# st-link-v2.net
KiCad netlist of a schematic drawn in Altium Designer
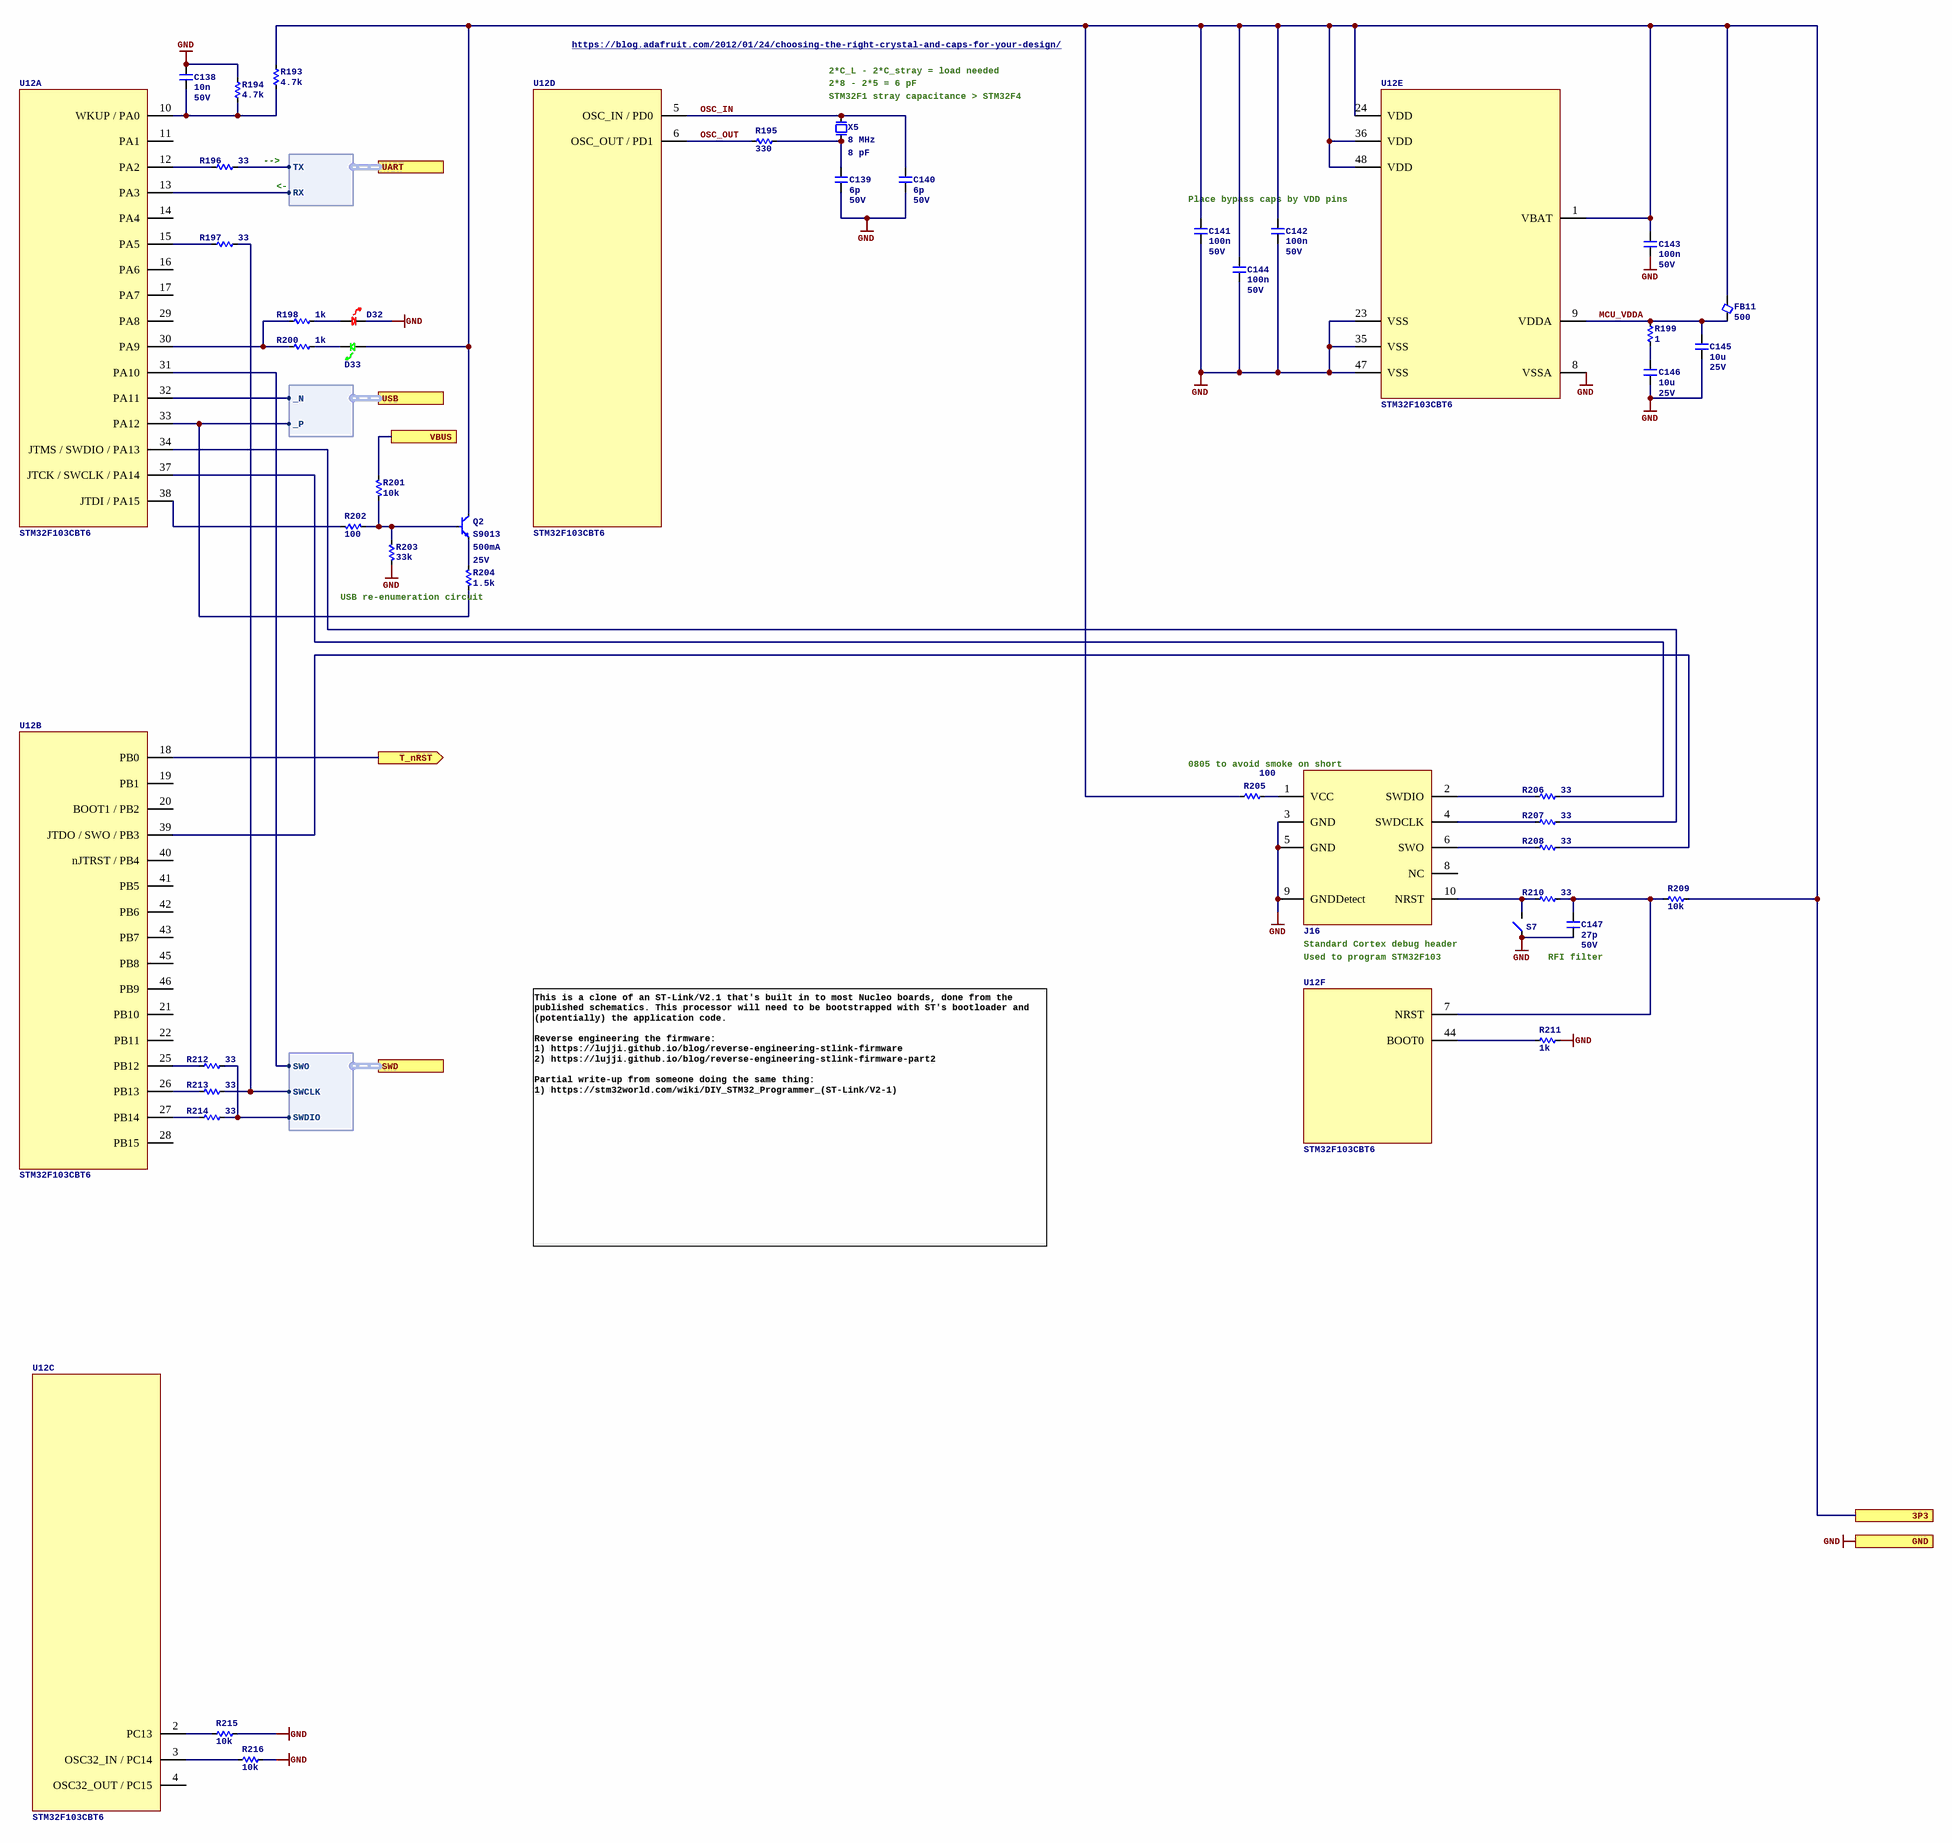
[diagram p0: st-link-v2.SchDoc]

(export (version "E")
  (design (tool "Eeschema 10.0.6"))
  (components
    (comp (ref "C138")
      (value "CL05B103KB5NNNC")
      (footprint "C0402")
      (fields
        (field (name "CAPACITANCE") "10n")
        (field (name "MANUFACTURER") "Samsung Electro-Mechanics")
        (field (name "VOLTAGE RATING") "50V")
      )
      (libsource (lib "database") (part "__template_cap"))
    )
    (comp (ref "C139")
      (value "0402CG6R0C500NT")
      (footprint "C0402")
      (fields
        (field (name "CAPACITANCE") "6p")
        (field (name "MANUFACTURER") "FH(Guangdong Fenghua Advanced Tech)")
        (field (name "VOLTAGE RATING") "50V")
      )
      (libsource (lib "database") (part "__template_cap"))
    )
    (comp (ref "C140")
      (value "0402CG6R0C500NT")
      (footprint "C0402")
      (fields
        (field (name "CAPACITANCE") "6p")
        (field (name "MANUFACTURER") "FH(Guangdong Fenghua Advanced Tech)")
        (field (name "VOLTAGE RATING") "50V")
      )
      (libsource (lib "database") (part "__template_cap"))
    )
    (comp (ref "C141")
      (value "CL05B104KB54PNC")
      (footprint "C0402")
      (fields
        (field (name "CAPACITANCE") "100n")
        (field (name "MANUFACTURER") "Samsung Electro-Mechanics")
        (field (name "VOLTAGE RATING") "50V")
      )
      (libsource (lib "database") (part "__template_cap"))
    )
    (comp (ref "C142")
      (value "CL05B104KB54PNC")
      (footprint "C0402")
      (fields
        (field (name "CAPACITANCE") "100n")
        (field (name "MANUFACTURER") "Samsung Electro-Mechanics")
        (field (name "VOLTAGE RATING") "50V")
      )
      (libsource (lib "database") (part "__template_cap"))
    )
    (comp (ref "C143")
      (value "CL05B104KB54PNC")
      (footprint "C0402")
      (fields
        (field (name "CAPACITANCE") "100n")
        (field (name "MANUFACTURER") "Samsung Electro-Mechanics")
        (field (name "VOLTAGE RATING") "50V")
      )
      (libsource (lib "database") (part "__template_cap"))
    )
    (comp (ref "C144")
      (value "CL05B104KB54PNC")
      (footprint "C0402")
      (fields
        (field (name "CAPACITANCE") "100n")
        (field (name "MANUFACTURER") "Samsung Electro-Mechanics")
        (field (name "VOLTAGE RATING") "50V")
      )
      (libsource (lib "database") (part "__template_cap"))
    )
    (comp (ref "C145")
      (value "CL10A106MA8NRNC")
      (footprint "C0603")
      (fields
        (field (name "CAPACITANCE") "10u")
        (field (name "MANUFACTURER") "Samsung Electro-Mechanics")
        (field (name "VOLTAGE RATING") "25V")
      )
      (libsource (lib "database") (part "__template_cap"))
    )
    (comp (ref "C146")
      (value "CL21B106KAYQNNE")
      (footprint "C0805")
      (fields
        (field (name "CAPACITANCE") "10u")
        (field (name "MANUFACTURER") "Samsung Electro-Mechanics")
        (field (name "VOLTAGE RATING") "25V")
      )
      (libsource (lib "database") (part "__template_cap"))
    )
    (comp (ref "C147")
      (value "0402CG270J500NT")
      (footprint "C0402")
      (fields
        (field (name "CAPACITANCE") "27p")
        (field (name "MANUFACTURER") "FH(Guangdong Fenghua Advanced Tech)")
        (field (name "VOLTAGE RATING") "50V")
      )
      (libsource (lib "database") (part "__template_cap"))
    )
    (comp (ref "D32")
      (value "LTST-C190KRKT")
      (footprint "LED_0603P_RED")
      (description "LED SUPER RED CLEAR 0603 SMD")
      (fields (field (name "MANUFACTURER") "Lite-On Inc"))
      (libsource (lib "SSCP") (part "LED_0603_RED_LTST-C190KRKT"))
    )
    (comp (ref "D33")
      (value "LTST-C190GKT")
      (footprint "LED_0603P_GREEN")
      (description "LED GREEN CLEAR 0603 SMD")
      (fields (field (name "MANUFACTURER") "Lite-On Inc"))
      (libsource (lib "SSCP") (part "LED_0603_GREEN_LTST-C190GKT"))
    )
    (comp (ref "FB11")
      (value "BLM15AX601SN1D")
      (footprint "FB0402")
      (fields (field (name "MANUFACTURER") "Murata Electronics") (field (name "CURRENT RATING (MA)") "500"))
      (libsource (lib "database") (part "__template_fb"))
    )
    (comp (ref "J16")
      (value "FTSH-105-01-L-DV-K")
      (footprint "FTSH-105-01-L-DV-K_KEYED")
      (description "CONN HEADER 10 POS DUAL .05\" SMD")
      (fields (field (name "MANUFACTURER") "Samtec Inc"))
      (libsource (lib "SSCP") (part "CONN_SWD_CORTEX_DEBUG"))
    )
    (comp (ref "Q2")
      (value "S9013")
      (footprint "3SOT23")
      (description "Bipolar (BJT) Transistor NPN 25 V 500 mA 150MHz 300 mW Surface Mount SOT-23")
      (fields
        (field (name "MANUFACTURER") "Shenzhen Slkormicro Semicon Co., Ltd.")
        (field (name "CURRENT") "500mA")
        (field (name "VOLTAGE") "25V")
      )
      (libsource (lib "SSCP") (part "NPN_25V_S9013"))
    )
    (comp (ref "R193")
      (value "4.7k")
      (footprint "R0402")
      (fields
        (field (name "TOLERANCE") "1%")
        (field (name "MANUFACTURER PART NUMBER") "0402WGF4701TCE")
        (field (name "MANUFACTURER") "UNI-ROYAL(Uniroyal Elec)")
      )
      (libsource (lib "database") (part "__template_resistor"))
    )
    (comp (ref "R194")
      (value "4.7k")
      (footprint "R0402")
      (fields
        (field (name "TOLERANCE") "1%")
        (field (name "MANUFACTURER PART NUMBER") "0402WGF4701TCE")
        (field (name "MANUFACTURER") "UNI-ROYAL(Uniroyal Elec)")
      )
      (libsource (lib "database") (part "__template_resistor"))
    )
    (comp (ref "R195")
      (value "330")
      (footprint "R0402")
      (fields
        (field (name "TOLERANCE") "1%")
        (field (name "MANUFACTURER PART NUMBER") "0402WGF3300TCE")
        (field (name "MANUFACTURER") "UNI-ROYAL(Uniroyal Elec)")
      )
      (libsource (lib "database") (part "__template_resistor"))
    )
    (comp (ref "R196")
      (value "33")
      (footprint "R0402")
      (fields
        (field (name "TOLERANCE") "1%")
        (field (name "MANUFACTURER PART NUMBER") "0402WGF330JTCE")
        (field (name "MANUFACTURER") "UNI-ROYAL(Uniroyal Elec)")
      )
      (libsource (lib "database") (part "__template_resistor"))
    )
    (comp (ref "R197")
      (value "33")
      (footprint "R0402")
      (fields
        (field (name "TOLERANCE") "1%")
        (field (name "MANUFACTURER PART NUMBER") "0402WGF330JTCE")
        (field (name "MANUFACTURER") "UNI-ROYAL(Uniroyal Elec)")
      )
      (libsource (lib "database") (part "__template_resistor"))
    )
    (comp (ref "R198")
      (value "1k")
      (footprint "R0402")
      (fields
        (field (name "TOLERANCE") "1%")
        (field (name "MANUFACTURER PART NUMBER") "0402WGF1001TCE")
        (field (name "MANUFACTURER") "UNI-ROYAL(Uniroyal Elec)")
      )
      (libsource (lib "database") (part "__template_resistor"))
    )
    (comp (ref "R199")
      (value "1")
      (footprint "R0402")
      (fields
        (field (name "TOLERANCE") "1%")
        (field (name "MANUFACTURER PART NUMBER") "CRCW04021R00FKED")
        (field (name "MANUFACTURER") "Vishay Intertech")
      )
      (libsource (lib "database") (part "__template_resistor"))
    )
    (comp (ref "R200")
      (value "1k")
      (footprint "R0402")
      (fields
        (field (name "TOLERANCE") "1%")
        (field (name "MANUFACTURER PART NUMBER") "0402WGF1001TCE")
        (field (name "MANUFACTURER") "UNI-ROYAL(Uniroyal Elec)")
      )
      (libsource (lib "database") (part "__template_resistor"))
    )
    (comp (ref "R201")
      (value "10k")
      (footprint "R0402")
      (fields
        (field (name "TOLERANCE") "1%")
        (field (name "MANUFACTURER PART NUMBER") "0402WGF1002TCE")
        (field (name "MANUFACTURER") "UNI-ROYAL(Uniroyal Elec)")
      )
      (libsource (lib "database") (part "__template_resistor"))
    )
    (comp (ref "R202")
      (value "100")
      (footprint "R0402")
      (fields
        (field (name "TOLERANCE") "1%")
        (field (name "MANUFACTURER PART NUMBER") "RC0402FR-07100RL")
        (field (name "MANUFACTURER") "YAGEO")
      )
      (libsource (lib "database") (part "__template_resistor"))
    )
    (comp (ref "R203")
      (value "33k")
      (footprint "R0402")
      (fields
        (field (name "TOLERANCE") "1%")
        (field (name "MANUFACTURER PART NUMBER") "0402WGF3302TCE")
        (field (name "MANUFACTURER") "UNI-ROYAL(Uniroyal Elec)")
      )
      (libsource (lib "database") (part "__template_resistor"))
    )
    (comp (ref "R204")
      (value "1.5k")
      (footprint "R0402")
      (fields
        (field (name "TOLERANCE") "1%")
        (field (name "MANUFACTURER PART NUMBER") "0402WGF1501TCE")
        (field (name "MANUFACTURER") "UNI-ROYAL(Uniroyal Elec)")
      )
      (libsource (lib "database") (part "__template_resistor"))
    )
    (comp (ref "R205")
      (value "100")
      (footprint "R0805")
      (fields
        (field (name "TOLERANCE") "1%")
        (field (name "MANUFACTURER PART NUMBER") "ERJP06F1000V")
        (field (name "MANUFACTURER") "PANASONIC")
      )
      (libsource (lib "database") (part "__template_resistor"))
    )
    (comp (ref "R206")
      (value "33")
      (footprint "R0402")
      (fields
        (field (name "TOLERANCE") "1%")
        (field (name "MANUFACTURER PART NUMBER") "0402WGF330JTCE")
        (field (name "MANUFACTURER") "UNI-ROYAL(Uniroyal Elec)")
      )
      (libsource (lib "database") (part "__template_resistor"))
    )
    (comp (ref "R207")
      (value "33")
      (footprint "R0402")
      (fields
        (field (name "TOLERANCE") "1%")
        (field (name "MANUFACTURER PART NUMBER") "0402WGF330JTCE")
        (field (name "MANUFACTURER") "UNI-ROYAL(Uniroyal Elec)")
      )
      (libsource (lib "database") (part "__template_resistor"))
    )
    (comp (ref "R208")
      (value "33")
      (footprint "R0402")
      (fields
        (field (name "TOLERANCE") "1%")
        (field (name "MANUFACTURER PART NUMBER") "0402WGF330JTCE")
        (field (name "MANUFACTURER") "UNI-ROYAL(Uniroyal Elec)")
      )
      (libsource (lib "database") (part "__template_resistor"))
    )
    (comp (ref "R209")
      (value "10k")
      (footprint "R0402")
      (fields
        (field (name "TOLERANCE") "1%")
        (field (name "MANUFACTURER PART NUMBER") "0402WGF1002TCE")
        (field (name "MANUFACTURER") "UNI-ROYAL(Uniroyal Elec)")
      )
      (libsource (lib "database") (part "__template_resistor"))
    )
    (comp (ref "R210")
      (value "33")
      (footprint "R0402")
      (fields
        (field (name "TOLERANCE") "1%")
        (field (name "MANUFACTURER PART NUMBER") "0402WGF330JTCE")
        (field (name "MANUFACTURER") "UNI-ROYAL(Uniroyal Elec)")
      )
      (libsource (lib "database") (part "__template_resistor"))
    )
    (comp (ref "R211")
      (value "1k")
      (footprint "R0402")
      (fields
        (field (name "TOLERANCE") "1%")
        (field (name "MANUFACTURER PART NUMBER") "0402WGF1001TCE")
        (field (name "MANUFACTURER") "UNI-ROYAL(Uniroyal Elec)")
      )
      (libsource (lib "database") (part "__template_resistor"))
    )
    (comp (ref "R212")
      (value "33")
      (footprint "R0402")
      (fields
        (field (name "TOLERANCE") "1%")
        (field (name "MANUFACTURER PART NUMBER") "0402WGF330JTCE")
        (field (name "MANUFACTURER") "UNI-ROYAL(Uniroyal Elec)")
      )
      (libsource (lib "database") (part "__template_resistor"))
    )
    (comp (ref "R213")
      (value "33")
      (footprint "R0402")
      (fields
        (field (name "TOLERANCE") "1%")
        (field (name "MANUFACTURER PART NUMBER") "0402WGF330JTCE")
        (field (name "MANUFACTURER") "UNI-ROYAL(Uniroyal Elec)")
      )
      (libsource (lib "database") (part "__template_resistor"))
    )
    (comp (ref "R214")
      (value "33")
      (footprint "R0402")
      (fields
        (field (name "TOLERANCE") "1%")
        (field (name "MANUFACTURER PART NUMBER") "0402WGF330JTCE")
        (field (name "MANUFACTURER") "UNI-ROYAL(Uniroyal Elec)")
      )
      (libsource (lib "database") (part "__template_resistor"))
    )
    (comp (ref "R215")
      (value "10k")
      (footprint "R0402")
      (fields
        (field (name "TOLERANCE") "1%")
        (field (name "MANUFACTURER PART NUMBER") "0402WGF1002TCE")
        (field (name "MANUFACTURER") "UNI-ROYAL(Uniroyal Elec)")
      )
      (libsource (lib "database") (part "__template_resistor"))
    )
    (comp (ref "R216")
      (value "10k")
      (footprint "R0402")
      (fields
        (field (name "TOLERANCE") "1%")
        (field (name "MANUFACTURER PART NUMBER") "0402WGF1002TCE")
        (field (name "MANUFACTURER") "UNI-ROYAL(Uniroyal Elec)")
      )
      (libsource (lib "database") (part "__template_resistor"))
    )
    (comp (ref "S7")
      (value "TS-1092S-B3D2-G")
      (footprint "SWITCH_TS-1092S-B3D2-G")
      (description "SWITCH TACTILE SPST-NO")
      (fields (field (name "MANUFACTURER") "Yuandi"))
      (libsource (lib "SSCP") (part "SWITCH_TS-1092S-B3D2-G"))
    )
    (comp (ref "U12")
      (value "STM32F103CBT6")
      (footprint "48TQFP7")
      (description "ARM Cortex-M3 STM32 F1 Microcontroller 32-Bit 72MHz 128kB FLASH LQFP48 STM32F103CBT6")
      (fields (field (name "MANUFACTURER") "STMicroelectronics"))
      (libsource (lib "SSCP") (part "MCU_STM32F103CBT6"))
    )
    (comp (ref "X5")
      (value "ECS-80-8-33Q-JES-TR")
      (footprint "4_SMD_3.2X2.5MM")
      (description "8 MHz ±20ppm Crystal 8pF 500 Ohms 4-SMD, No Lead")
      (fields
        (field (name "MANUFACTURER") "ECS Inc.")
        (field (name "FREQUENCY") "8 MHz")
        (field (name "CAPACITANCE") "8 pF")
      )
      (libsource (lib "SSCP") (part "XTAL_8MHZ_ECS-80-8-33Q-JES-TR"))
    )
  )
  (nets
    (net (code "4") (name "/3P3") (class "Default")
      (node (ref "C141") (pin "1") (pintype "passive"))
      (node (ref "C142") (pin "1") (pintype "passive"))
      (node (ref "C143") (pin "1") (pintype "passive"))
      (node (ref "C144") (pin "1") (pintype "passive"))
      (node (ref "D33") (pin "2") (pintype "passive"))
      (node (ref "FB11") (pin "2") (pintype "passive"))
      (node (ref "Q2") (pin "3") (pinfunction "C_3") (pintype "passive"))
      (node (ref "R193") (pin "2") (pintype "passive"))
      (node (ref "R205") (pin "2") (pintype "passive"))
      (node (ref "R209") (pin "1") (pintype "passive"))
      (node (ref "U12") (pin "1") (pinfunction "VBAT_1") (pintype "passive"))
      (node (ref "U12") (pin "24") (pinfunction "VDD_24") (pintype "passive"))
      (node (ref "U12") (pin "36") (pinfunction "VDD_36") (pintype "passive"))
      (node (ref "U12") (pin "48") (pinfunction "VDD_48") (pintype "passive"))
    )
    (net (code "5") (name "/MCU_VDDA") (class "Default")
      (node (ref "C145") (pin "1") (pintype "passive"))
      (node (ref "FB11") (pin "1") (pintype "passive"))
      (node (ref "R199") (pin "2") (pintype "passive"))
      (node (ref "U12") (pin "9") (pinfunction "VDDA_9") (pintype "passive"))
    )
    (net (code "6") (name "/OSC_IN") (class "Default")
      (node (ref "C140") (pin "1") (pintype "passive"))
      (node (ref "U12") (pin "5") (pinfunction "OSC_IN_/_PD0_5") (pintype "passive"))
      (node (ref "X5") (pin "3") (pinfunction "3_3") (pintype "passive"))
    )
    (net (code "7") (name "/OSC_OUT") (class "Default")
      (node (ref "R195") (pin "1") (pintype "passive"))
      (node (ref "U12") (pin "6") (pinfunction "OSC_OUT_/_PD1_6") (pintype "passive"))
    )
    (net (code "8") (name "/RX") (class "Default")
      (node (ref "U12") (pin "13") (pinfunction "PA3_13") (pintype "passive"))
    )
    (net (code "9") (name "/SWCLK") (class "Default")
      (node (ref "R197") (pin "1") (pintype "passive"))
      (node (ref "R213") (pin "1") (pintype "passive"))
    )
    (net (code "10") (name "/SWDIO") (class "Default")
      (node (ref "R212") (pin "1") (pintype "passive"))
      (node (ref "R214") (pin "1") (pintype "passive"))
    )
    (net (code "11") (name "/SWO") (class "Default")
      (node (ref "U12") (pin "31") (pinfunction "PA10_31") (pintype "passive"))
    )
    (net (code "12") (name "/TX") (class "Default") (node (ref "R196") (pin "1") (pintype "passive")))
    (net (code "13") (name "/T_nRST") (class "Default")
      (node (ref "U12") (pin "18") (pinfunction "PB0_18") (pintype "passive"))
    )
    (net (code "14") (name "/VBUS") (class "Default") (node (ref "R201") (pin "1") (pintype "passive")))
    (net (code "15") (name "/_N") (class "Default")
      (node (ref "U12") (pin "32") (pinfunction "PA11_32") (pintype "passive"))
    )
    (net (code "16") (name "/_P") (class "Default")
      (node (ref "R204") (pin "2") (pintype "passive"))
      (node (ref "U12") (pin "33") (pinfunction "PA12_33") (pintype "passive"))
    )
    (net (code "20") (name "GND") (class "Default")
      (node (ref "C138") (pin "1") (pintype "passive"))
      (node (ref "C139") (pin "2") (pintype "passive"))
      (node (ref "C140") (pin "2") (pintype "passive"))
      (node (ref "C141") (pin "2") (pintype "passive"))
      (node (ref "C142") (pin "2") (pintype "passive"))
      (node (ref "C143") (pin "2") (pintype "passive"))
      (node (ref "C144") (pin "2") (pintype "passive"))
      (node (ref "C145") (pin "2") (pintype "passive"))
      (node (ref "C146") (pin "2") (pintype "passive"))
      (node (ref "C147") (pin "2") (pintype "passive"))
      (node (ref "D32") (pin "1") (pintype "passive"))
      (node (ref "J16") (pin "3") (pinfunction "GND_3") (pintype "passive"))
      (node (ref "J16") (pin "5") (pinfunction "GND_5") (pintype "passive"))
      (node (ref "J16") (pin "9") (pinfunction "GNDDetect_9") (pintype "passive"))
      (node (ref "R194") (pin "2") (pintype "passive"))
      (node (ref "R203") (pin "2") (pintype "passive"))
      (node (ref "R211") (pin "2") (pintype "passive"))
      (node (ref "R215") (pin "2") (pintype "passive"))
      (node (ref "R216") (pin "2") (pintype "passive"))
      (node (ref "S7") (pin "1") (pintype "passive"))
      (node (ref "U12") (pin "23") (pinfunction "VSS_23") (pintype "passive"))
      (node (ref "U12") (pin "35") (pinfunction "VSS_35") (pintype "passive"))
      (node (ref "U12") (pin "47") (pinfunction "VSS_47") (pintype "passive"))
      (node (ref "U12") (pin "8") (pinfunction "VSSA_8") (pintype "passive"))
    )
    (net (code "21") (name "Net-(C139-Pad1)") (class "Default")
      (node (ref "C139") (pin "1") (pintype "passive"))
      (node (ref "R195") (pin "2") (pintype "passive"))
      (node (ref "X5") (pin "1") (pinfunction "1_1") (pintype "passive"))
    )
    (net (code "22") (name "Net-(C146-Pad1)") (class "Default")
      (node (ref "C146") (pin "1") (pintype "passive"))
      (node (ref "R199") (pin "1") (pintype "passive"))
    )
    (net (code "23") (name "Net-(D32-Pad2)") (class "Default")
      (node (ref "D32") (pin "2") (pintype "passive"))
      (node (ref "R198") (pin "1") (pintype "passive"))
    )
    (net (code "24") (name "Net-(D33-Pad1)") (class "Default")
      (node (ref "D33") (pin "1") (pintype "passive"))
      (node (ref "R200") (pin "1") (pintype "passive"))
    )
    (net (code "25") (name "Net-(J16-NRST)") (class "Default")
      (node (ref "J16") (pin "10") (pinfunction "NRST_10") (pintype "passive"))
      (node (ref "R210") (pin "2") (pintype "passive"))
      (node (ref "S7") (pin "2") (pintype "passive"))
    )
    (net (code "26") (name "Net-(J16-SWDCLK)") (class "Default")
      (node (ref "J16") (pin "4") (pinfunction "SWDCLK_4") (pintype "passive"))
      (node (ref "R207") (pin "2") (pintype "passive"))
    )
    (net (code "27") (name "Net-(J16-SWDIO)") (class "Default")
      (node (ref "J16") (pin "2") (pinfunction "SWDIO_2") (pintype "passive"))
      (node (ref "R206") (pin "2") (pintype "passive"))
    )
    (net (code "28") (name "Net-(J16-SWO)") (class "Default")
      (node (ref "J16") (pin "6") (pinfunction "SWO_6") (pintype "passive"))
      (node (ref "R208") (pin "2") (pintype "passive"))
    )
    (net (code "29") (name "Net-(J16-VCC)") (class "Default")
      (node (ref "J16") (pin "1") (pinfunction "VCC_1") (pintype "passive"))
      (node (ref "R205") (pin "1") (pintype "passive"))
    )
    (net (code "30") (name "Net-(Q2-B)") (class "Default")
      (node (ref "Q2") (pin "1") (pinfunction "B_1") (pintype "passive"))
      (node (ref "R201") (pin "2") (pintype "passive"))
      (node (ref "R202") (pin "1") (pintype "passive"))
      (node (ref "R203") (pin "1") (pintype "passive"))
    )
    (net (code "31") (name "Net-(Q2-E)") (class "Default")
      (node (ref "Q2") (pin "2") (pinfunction "E_2") (pintype "passive"))
      (node (ref "R204") (pin "1") (pintype "passive"))
    )
    (net (code "32") (name "Net-(U12A-JTCK_{slash}_SWCLK_{slash}_PA14)") (class "Default")
      (node (ref "R206") (pin "1") (pintype "passive"))
      (node (ref "U12") (pin "37") (pinfunction "JTCK_/_SWCLK_/_PA14_37") (pintype "passive"))
    )
    (net (code "33") (name "Net-(U12A-JTDI_{slash}_PA15)") (class "Default")
      (node (ref "R202") (pin "2") (pintype "passive"))
      (node (ref "U12") (pin "38") (pinfunction "JTDI_/_PA15_38") (pintype "passive"))
    )
    (net (code "34") (name "Net-(U12A-JTMS_{slash}_SWDIO_{slash}_PA13)") (class "Default")
      (node (ref "R207") (pin "1") (pintype "passive"))
      (node (ref "U12") (pin "34") (pinfunction "JTMS_/_SWDIO_/_PA13_34") (pintype "passive"))
    )
    (net (code "35") (name "Net-(U12A-PA2)") (class "Default")
      (node (ref "R196") (pin "2") (pintype "passive"))
      (node (ref "U12") (pin "12") (pinfunction "PA2_12") (pintype "passive"))
    )
    (net (code "36") (name "Net-(U12A-PA5)") (class "Default")
      (node (ref "R197") (pin "2") (pintype "passive"))
      (node (ref "U12") (pin "15") (pinfunction "PA5_15") (pintype "passive"))
    )
    (net (code "37") (name "Net-(U12A-PA9)") (class "Default")
      (node (ref "R198") (pin "2") (pintype "passive"))
      (node (ref "R200") (pin "2") (pintype "passive"))
      (node (ref "U12") (pin "30") (pinfunction "PA9_30") (pintype "passive"))
    )
    (net (code "38") (name "Net-(U12A-WKUP_{slash}_PA0)") (class "Default")
      (node (ref "C138") (pin "2") (pintype "passive"))
      (node (ref "R193") (pin "1") (pintype "passive"))
      (node (ref "R194") (pin "1") (pintype "passive"))
      (node (ref "U12") (pin "10") (pinfunction "WKUP_/_PA0_10") (pintype "passive"))
    )
    (net (code "39") (name "Net-(U12B-JTDO_{slash}_SWO_{slash}_PB3)") (class "Default")
      (node (ref "R208") (pin "1") (pintype "passive"))
      (node (ref "U12") (pin "39") (pinfunction "JTDO_/_SWO_/_PB3_39") (pintype "passive"))
    )
    (net (code "40") (name "Net-(U12B-PB12)") (class "Default")
      (node (ref "R212") (pin "2") (pintype "passive"))
      (node (ref "U12") (pin "25") (pinfunction "PB12_25") (pintype "passive"))
    )
    (net (code "41") (name "Net-(U12B-PB13)") (class "Default")
      (node (ref "R213") (pin "2") (pintype "passive"))
      (node (ref "U12") (pin "26") (pinfunction "PB13_26") (pintype "passive"))
    )
    (net (code "42") (name "Net-(U12B-PB14)") (class "Default")
      (node (ref "R214") (pin "2") (pintype "passive"))
      (node (ref "U12") (pin "27") (pinfunction "PB14_27") (pintype "passive"))
    )
    (net (code "43") (name "Net-(U12C-OSC32_IN_{slash}_PC14)") (class "Default")
      (node (ref "R216") (pin "1") (pintype "passive"))
      (node (ref "U12") (pin "3") (pinfunction "OSC32_IN_/_PC14_3") (pintype "passive"))
    )
    (net (code "44") (name "Net-(U12C-PC13)") (class "Default")
      (node (ref "R215") (pin "1") (pintype "passive"))
      (node (ref "U12") (pin "2") (pinfunction "PC13_2") (pintype "passive"))
    )
    (net (code "45") (name "Net-(U12F-BOOT0)") (class "Default")
      (node (ref "R211") (pin "1") (pintype "passive"))
      (node (ref "U12") (pin "44") (pinfunction "BOOT0_44") (pintype "passive"))
    )
    (net (code "46") (name "Net-(U12F-NRST)") (class "Default")
      (node (ref "C147") (pin "1") (pintype "passive"))
      (node (ref "R209") (pin "2") (pintype "passive"))
      (node (ref "R210") (pin "1") (pintype "passive"))
      (node (ref "U12") (pin "7") (pinfunction "NRST_7") (pintype "passive"))
    )
    (net (code "47") (name "unconnected-(J16-NC-Pad8)") (class "Default")
      (node (ref "J16") (pin "8") (pinfunction "NC_8") (pintype "passive"))
    )
    (net (code "48") (name "unconnected-(U12A-PA1-Pad11)") (class "Default")
      (node (ref "U12") (pin "11") (pinfunction "PA1_11") (pintype "passive"))
    )
    (net (code "49") (name "unconnected-(U12A-PA4-Pad14)") (class "Default")
      (node (ref "U12") (pin "14") (pinfunction "PA4_14") (pintype "passive"))
    )
    (net (code "50") (name "unconnected-(U12A-PA6-Pad16)") (class "Default")
      (node (ref "U12") (pin "16") (pinfunction "PA6_16") (pintype "passive"))
    )
    (net (code "51") (name "unconnected-(U12A-PA7-Pad17)") (class "Default")
      (node (ref "U12") (pin "17") (pinfunction "PA7_17") (pintype "passive"))
    )
    (net (code "52") (name "unconnected-(U12A-PA8-Pad29)") (class "Default")
      (node (ref "U12") (pin "29") (pinfunction "PA8_29") (pintype "passive"))
    )
    (net (code "53") (name "unconnected-(U12B-BOOT1_{slash}_PB2-Pad20)") (class "Default")
      (node (ref "U12") (pin "20") (pinfunction "BOOT1_/_PB2_20") (pintype "passive"))
    )
    (net (code "54") (name "unconnected-(U12B-PB1-Pad19)") (class "Default")
      (node (ref "U12") (pin "19") (pinfunction "PB1_19") (pintype "passive"))
    )
    (net (code "55") (name "unconnected-(U12B-PB5-Pad41)") (class "Default")
      (node (ref "U12") (pin "41") (pinfunction "PB5_41") (pintype "passive"))
    )
    (net (code "56") (name "unconnected-(U12B-PB6-Pad42)") (class "Default")
      (node (ref "U12") (pin "42") (pinfunction "PB6_42") (pintype "passive"))
    )
    (net (code "57") (name "unconnected-(U12B-PB7-Pad43)") (class "Default")
      (node (ref "U12") (pin "43") (pinfunction "PB7_43") (pintype "passive"))
    )
    (net (code "58") (name "unconnected-(U12B-PB8-Pad45)") (class "Default")
      (node (ref "U12") (pin "45") (pinfunction "PB8_45") (pintype "passive"))
    )
    (net (code "59") (name "unconnected-(U12B-PB9-Pad46)") (class "Default")
      (node (ref "U12") (pin "46") (pinfunction "PB9_46") (pintype "passive"))
    )
    (net (code "60") (name "unconnected-(U12B-PB10-Pad21)") (class "Default")
      (node (ref "U12") (pin "21") (pinfunction "PB10_21") (pintype "passive"))
    )
    (net (code "61") (name "unconnected-(U12B-PB11-Pad22)") (class "Default")
      (node (ref "U12") (pin "22") (pinfunction "PB11_22") (pintype "passive"))
    )
    (net (code "62") (name "unconnected-(U12B-PB15-Pad28)") (class "Default")
      (node (ref "U12") (pin "28") (pinfunction "PB15_28") (pintype "passive"))
    )
    (net (code "63") (name "unconnected-(U12B-nJTRST_{slash}_PB4-Pad40)") (class "Default")
      (node (ref "U12") (pin "40") (pinfunction "nJTRST_/_PB4_40") (pintype "passive"))
    )
    (net (code "64") (name "unconnected-(U12C-OSC32_OUT_{slash}_PC15-Pad4)") (class "Default")
      (node (ref "U12") (pin "4") (pinfunction "OSC32_OUT_/_PC15_4") (pintype "passive"))
    )
  )
)
